# cs301_YourGroupNumber.net
KiCad netlist of a schematic drawn in Altium Designer
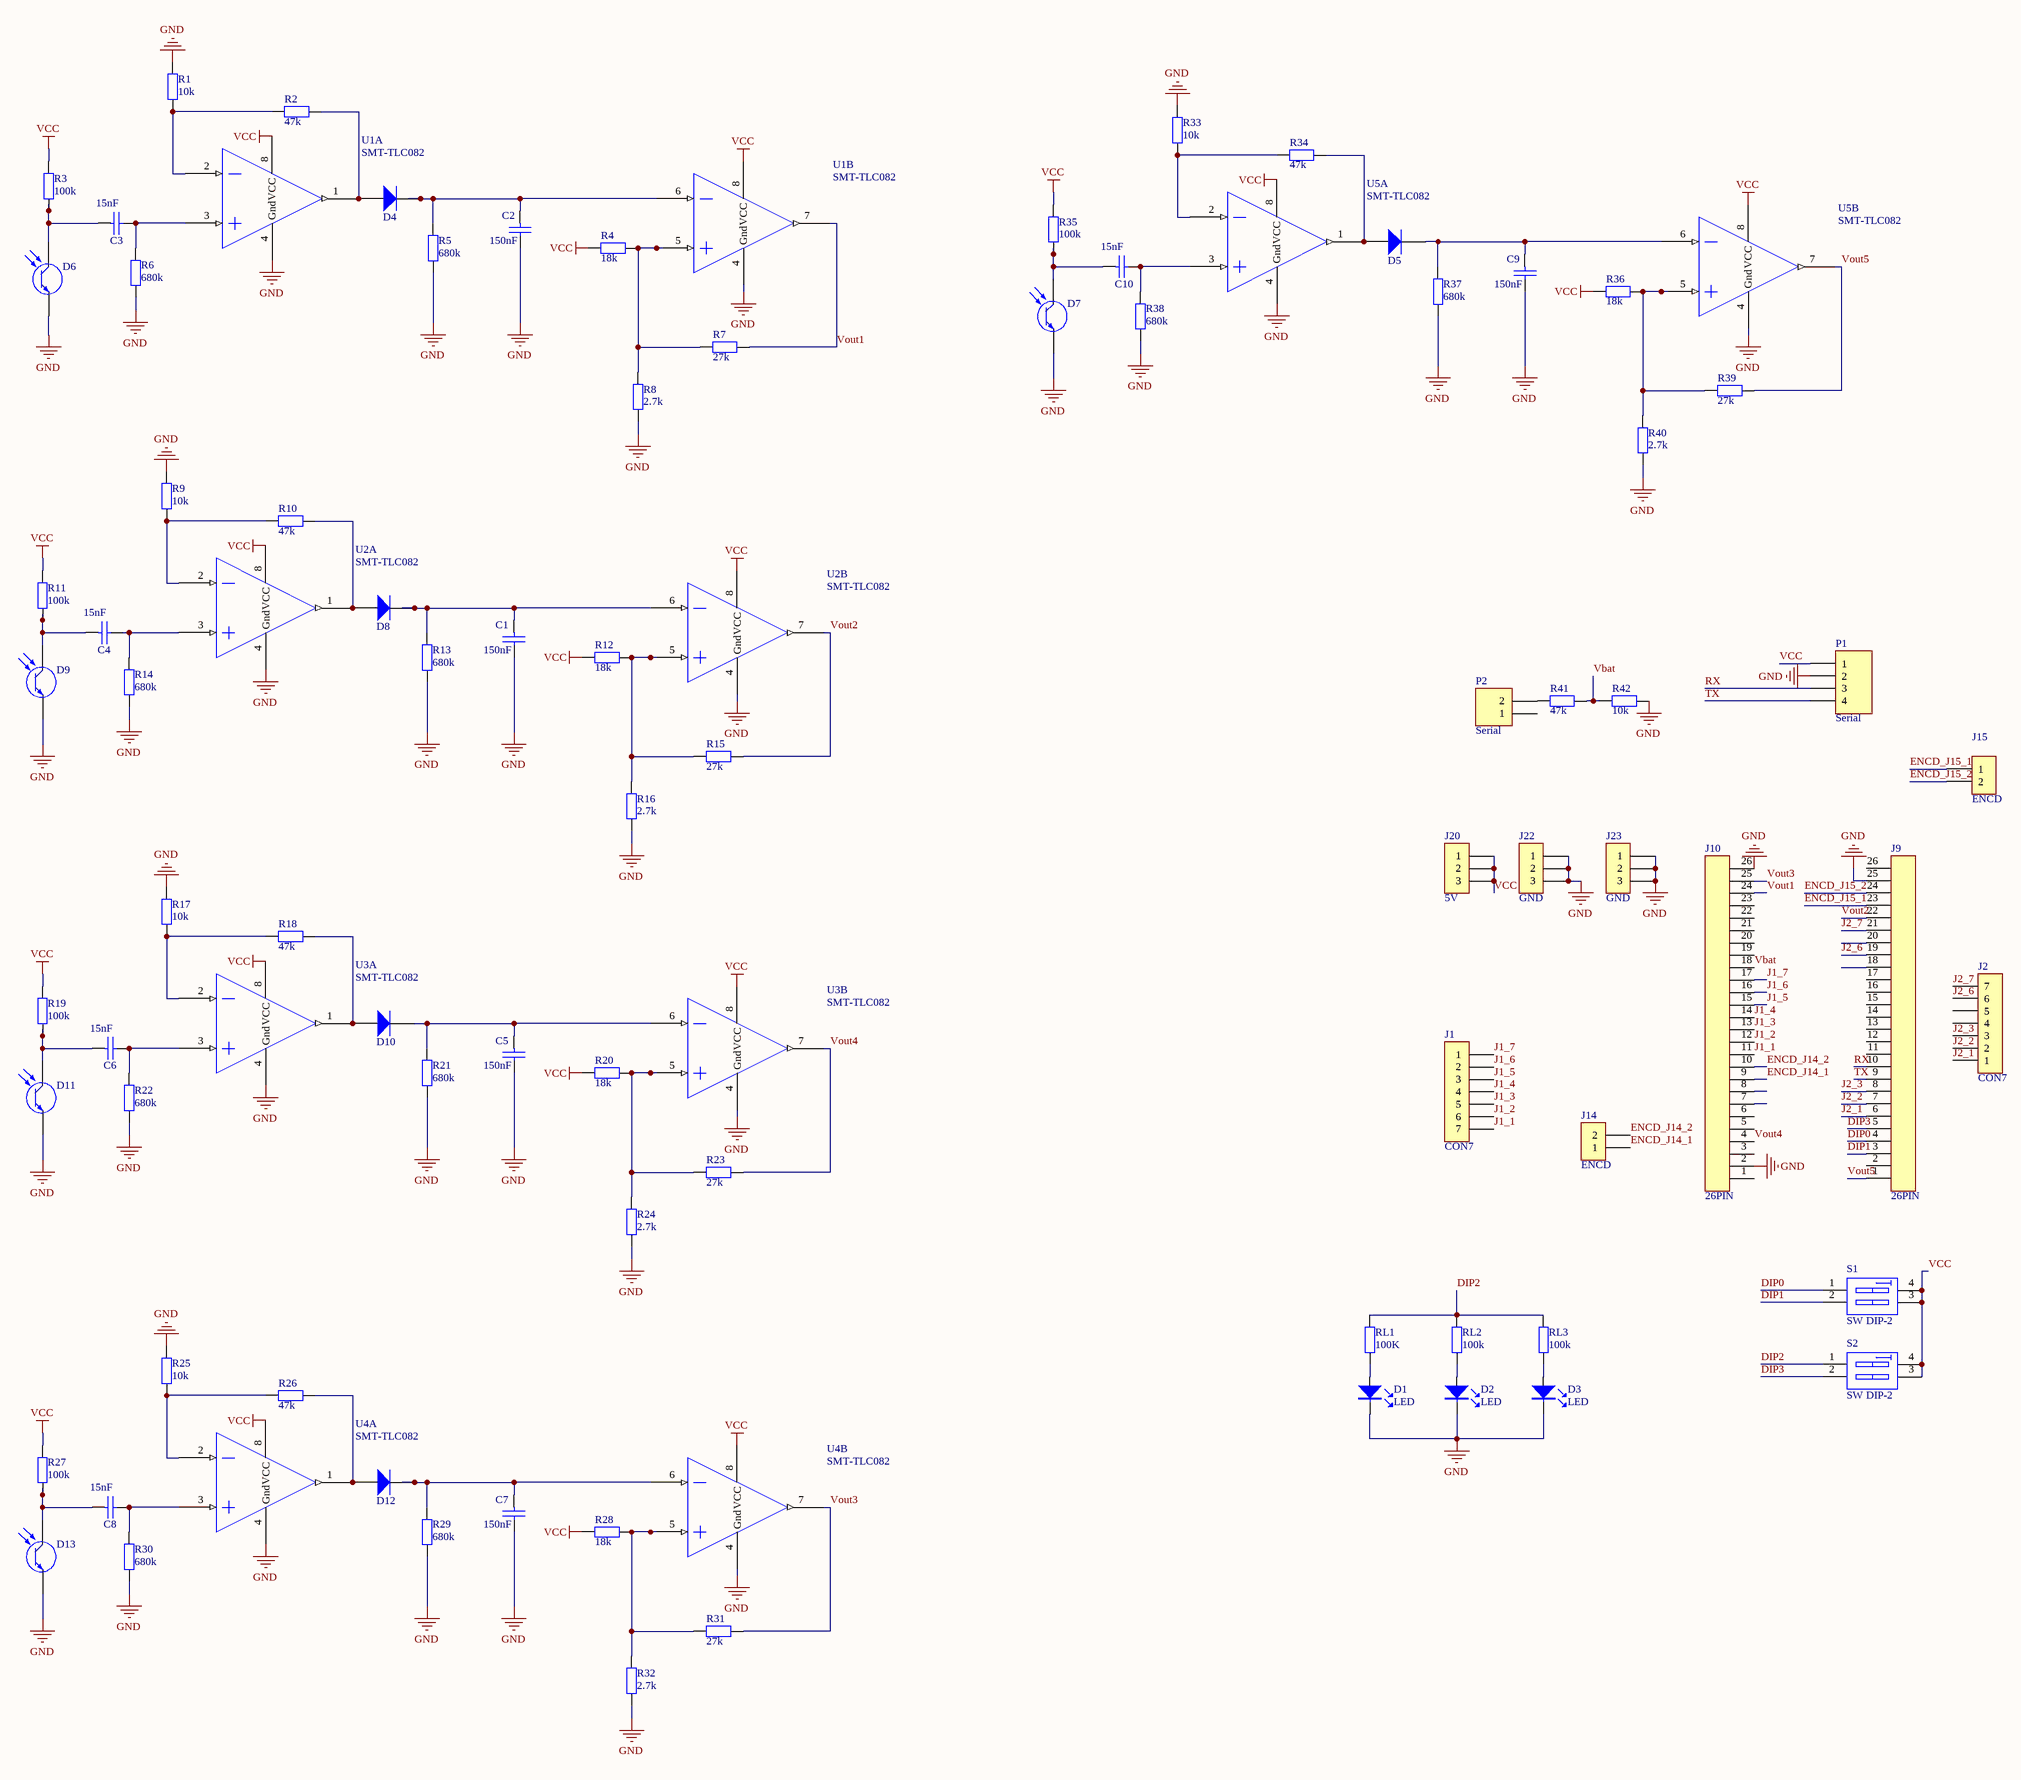
[diagram p0: cs301_YourGroupNumber.SchDoc]

(export (version "E")
  (design (tool "Eeschema 10.0.6"))
  (components
    (comp (ref "C1")
      (value "150nF")
      (footprint "ECE-CAPC1608-0603SM")
      (description "CAP CER 150nF 25V X7R SM0603")
      (libsource (lib "EceParts") (part "Cap"))
    )
    (comp (ref "C2")
      (value "150nF")
      (footprint "ECE-CAPC1608-0603SM")
      (description "CAP CER 150nF 25V X7R SM0603")
      (libsource (lib "EceParts") (part "Cap"))
    )
    (comp (ref "C3")
      (value "15nF")
      (footprint "ECE-CAPC1608-0603SM")
      (description "CAP CER 15nF 50V X7R SM0603")
      (libsource (lib "EceParts") (part "Cap"))
    )
    (comp (ref "C4")
      (value "15nF")
      (footprint "ECE-CAPC1608-0603SM")
      (description "CAP CER 15nF 50V X7R SM0603")
      (libsource (lib "EceParts") (part "Cap"))
    )
    (comp (ref "C5")
      (value "150nF")
      (footprint "ECE-CAPC1608-0603SM")
      (description "CAP CER 150nF 25V X7R SM0603")
      (libsource (lib "EceParts") (part "Cap"))
    )
    (comp (ref "C6")
      (value "15nF")
      (footprint "ECE-CAPC1608-0603SM")
      (description "CAP CER 15nF 50V X7R SM0603")
      (libsource (lib "EceParts") (part "Cap"))
    )
    (comp (ref "C7")
      (value "150nF")
      (footprint "ECE-CAPC1608-0603SM")
      (description "CAP CER 150nF 25V X7R SM0603")
      (libsource (lib "EceParts") (part "Cap"))
    )
    (comp (ref "C8")
      (value "15nF")
      (footprint "ECE-CAPC1608-0603SM")
      (description "CAP CER 15nF 50V X7R SM0603")
      (libsource (lib "EceParts") (part "Cap"))
    )
    (comp (ref "C9")
      (value "150nF")
      (footprint "ECE-CAPC1608-0603SM")
      (description "CAP CER 150nF 25V X7R SM0603")
      (libsource (lib "EceParts") (part "Cap"))
    )
    (comp (ref "C10")
      (value "15nF")
      (footprint "ECE-CAPC1608-0603SM")
      (description "CAP CER 15nF 50V X7R SM0603")
      (libsource (lib "EceParts") (part "Cap"))
    )
    (comp (ref "D1") (value "LED") (footprint "LED0.1/5MM") (libsource (lib "COMSYS301_2013") (part "LED")))
    (comp (ref "D2") (value "LED") (footprint "LED0.1/5MM") (libsource (lib "COMSYS301_2013") (part "LED")))
    (comp (ref "D3") (value "LED") (footprint "LED0.1/5MM") (libsource (lib "COMSYS301_2013") (part "LED")))
    (comp (ref "D4")
      (value "1N4148W-7-F")
      (footprint "ECE-DIO-SOD123SM")
      (description "DIODE GEN PURPOSE 300mA SM")
      (libsource (lib "EceParts") (part "Diode"))
    )
    (comp (ref "D5")
      (value "1N4148W-7-F")
      (footprint "ECE-DIO-SOD123SM")
      (description "DIODE GEN PURPOSE 300mA SM")
      (libsource (lib "EceParts") (part "Diode"))
    )
    (comp (ref "D6")
      (value "TEMT6200")
      (footprint "ECE-SENSOR-0805SM")
      (description "LIGHT SENSOR TEMT6200 SM")
      (libsource (lib "EceParts") (part "TEMT6200"))
    )
    (comp (ref "D7")
      (value "TEMT6200")
      (footprint "ECE-SENSOR-0805SM")
      (description "LIGHT SENSOR TEMT6200 SM")
      (libsource (lib "EceParts") (part "TEMT6200"))
    )
    (comp (ref "D8")
      (value "1N4148W-7-F")
      (footprint "ECE-DIO-SOD123SM")
      (description "DIODE GEN PURPOSE 300mA SM")
      (libsource (lib "EceParts") (part "Diode"))
    )
    (comp (ref "D9")
      (value "TEMT6200")
      (footprint "ECE-SENSOR-0805SM")
      (description "LIGHT SENSOR TEMT6200 SM")
      (libsource (lib "EceParts") (part "TEMT6200"))
    )
    (comp (ref "D10")
      (value "1N4148W-7-F")
      (footprint "ECE-DIO-SOD123SM")
      (description "DIODE GEN PURPOSE 300mA SM")
      (libsource (lib "EceParts") (part "Diode"))
    )
    (comp (ref "D11")
      (value "TEMT6200")
      (footprint "ECE-SENSOR-0805SM")
      (description "LIGHT SENSOR TEMT6200 SM")
      (libsource (lib "EceParts") (part "TEMT6200"))
    )
    (comp (ref "D12")
      (value "1N4148W-7-F")
      (footprint "ECE-DIO-SOD123SM")
      (description "DIODE GEN PURPOSE 300mA SM")
      (libsource (lib "EceParts") (part "Diode"))
    )
    (comp (ref "D13")
      (value "TEMT6200")
      (footprint "ECE-SENSOR-0805SM")
      (description "LIGHT SENSOR TEMT6200 SM")
      (libsource (lib "EceParts") (part "TEMT6200"))
    )
    (comp (ref "J1")
      (value "CON7")
      (footprint "SIP7")
      (description "Connector")
      (libsource (lib "") (part "CON7_1"))
    )
    (comp (ref "J2")
      (value "CON7")
      (footprint "SIP7")
      (description "Connector")
      (libsource (lib "Miscellaneous Devices") (part "CON7"))
    )
    (comp (ref "J9") (value "26PIN") (footprint "SIP26") (libsource (lib "") (part "26PIN_1")))
    (comp (ref "J10")
      (value "26PIN")
      (footprint "SIP26")
      (libsource (lib "Miscellaneous Devices") (part "26PIN"))
    )
    (comp (ref "J14")
      (value "ENCD")
      (footprint "sip2")
      (description "Connector")
      (libsource (lib "Miscellaneous Devices") (part "CON2"))
    )
    (comp (ref "J15")
      (value "ENCD")
      (footprint "sip2")
      (description "Connector")
      (libsource (lib "") (part "CON2_1"))
    )
    (comp (ref "J20")
      (value "5V")
      (footprint "sip3")
      (description "Connector")
      (libsource (lib "Miscellaneous Devices") (part "CON3"))
    )
    (comp (ref "J22")
      (value "GND")
      (footprint "sip3")
      (description "Connector")
      (libsource (lib "Miscellaneous Devices") (part "CON3"))
    )
    (comp (ref "J23")
      (value "GND")
      (footprint "sip3")
      (description "Connector")
      (libsource (lib "Miscellaneous Devices") (part "CON3"))
    )
    (comp (ref "P1")
      (value "Serial")
      (footprint "ece-HDR1X4")
      (description "Header, 4-Pin")
      (fields (field (name "PUBLISHER") "Altium Limited"))
      (libsource (lib "ece components") (part "Header 4"))
    )
    (comp (ref "P2")
      (value "Serial")
      (footprint "HDR1X2")
      (description "Header, 2-Pin")
      (fields (field (name "PUBLISHER") "Altium Limited"))
      (libsource (lib "Miscellaneous Connectors") (part "Header 2"))
    )
    (comp (ref "R1")
      (value "10k")
      (footprint "RESC2012-0805SM")
      (description "SM resistor")
      (libsource (lib "") (part "Res SM 0805_1"))
    )
    (comp (ref "R2")
      (value "47k")
      (footprint "RESC2012-0805SM")
      (description "SM resistor")
      (libsource (lib "ece components") (part "Res SM 0805"))
    )
    (comp (ref "R3")
      (value "100k")
      (footprint "RESC2012-0805SM")
      (description "SM resistor")
      (libsource (lib "") (part "Res SM 0805_1"))
    )
    (comp (ref "R4")
      (value "18k")
      (footprint "RESC2012-0805SM")
      (description "SM resistor")
      (libsource (lib "ece components") (part "Res SM 0805"))
    )
    (comp (ref "R5")
      (value "680k")
      (footprint "RESC2012-0805SM")
      (description "SM resistor")
      (libsource (lib "") (part "Res SM 0805_1"))
    )
    (comp (ref "R6")
      (value "680k")
      (footprint "RESC2012-0805SM")
      (description "SM resistor")
      (libsource (lib "") (part "Res SM 0805_1"))
    )
    (comp (ref "R7")
      (value "27k")
      (footprint "RESC2012-0805SM")
      (description "SM resistor")
      (libsource (lib "ece components") (part "Res SM 0805"))
    )
    (comp (ref "R8")
      (value "2.7k")
      (footprint "RESC2012-0805SM")
      (description "SM resistor")
      (libsource (lib "") (part "Res SM 0805_1"))
    )
    (comp (ref "R9")
      (value "10k")
      (footprint "RESC2012-0805SM")
      (description "SM resistor")
      (libsource (lib "") (part "Res SM 0805_1"))
    )
    (comp (ref "R10")
      (value "47k")
      (footprint "RESC2012-0805SM")
      (description "SM resistor")
      (libsource (lib "ece components") (part "Res SM 0805"))
    )
    (comp (ref "R11")
      (value "100k")
      (footprint "RESC2012-0805SM")
      (description "SM resistor")
      (libsource (lib "") (part "Res SM 0805_1"))
    )
    (comp (ref "R12")
      (value "18k")
      (footprint "RESC2012-0805SM")
      (description "SM resistor")
      (libsource (lib "ece components") (part "Res SM 0805"))
    )
    (comp (ref "R13")
      (value "680k")
      (footprint "RESC2012-0805SM")
      (description "SM resistor")
      (libsource (lib "") (part "Res SM 0805_1"))
    )
    (comp (ref "R14")
      (value "680k")
      (footprint "RESC2012-0805SM")
      (description "SM resistor")
      (libsource (lib "") (part "Res SM 0805_1"))
    )
    (comp (ref "R15")
      (value "27k")
      (footprint "RESC2012-0805SM")
      (description "SM resistor")
      (libsource (lib "ece components") (part "Res SM 0805"))
    )
    (comp (ref "R16")
      (value "2.7k")
      (footprint "RESC2012-0805SM")
      (description "SM resistor")
      (libsource (lib "") (part "Res SM 0805_1"))
    )
    (comp (ref "R17")
      (value "10k")
      (footprint "RESC2012-0805SM")
      (description "SM resistor")
      (libsource (lib "") (part "Res SM 0805_1"))
    )
    (comp (ref "R18")
      (value "47k")
      (footprint "RESC2012-0805SM")
      (description "SM resistor")
      (libsource (lib "ece components") (part "Res SM 0805"))
    )
    (comp (ref "R19")
      (value "100k")
      (footprint "RESC2012-0805SM")
      (description "SM resistor")
      (libsource (lib "") (part "Res SM 0805_1"))
    )
    (comp (ref "R20")
      (value "18k")
      (footprint "RESC2012-0805SM")
      (description "SM resistor")
      (libsource (lib "ece components") (part "Res SM 0805"))
    )
    (comp (ref "R21")
      (value "680k")
      (footprint "RESC2012-0805SM")
      (description "SM resistor")
      (libsource (lib "") (part "Res SM 0805_1"))
    )
    (comp (ref "R22")
      (value "680k")
      (footprint "RESC2012-0805SM")
      (description "SM resistor")
      (libsource (lib "") (part "Res SM 0805_1"))
    )
    (comp (ref "R23")
      (value "27k")
      (footprint "RESC2012-0805SM")
      (description "SM resistor")
      (libsource (lib "ece components") (part "Res SM 0805"))
    )
    (comp (ref "R24")
      (value "2.7k")
      (footprint "RESC2012-0805SM")
      (description "SM resistor")
      (libsource (lib "") (part "Res SM 0805_1"))
    )
    (comp (ref "R25")
      (value "10k")
      (footprint "RESC2012-0805SM")
      (description "SM resistor")
      (libsource (lib "") (part "Res SM 0805_1"))
    )
    (comp (ref "R26")
      (value "47k")
      (footprint "RESC2012-0805SM")
      (description "SM resistor")
      (libsource (lib "ece components") (part "Res SM 0805"))
    )
    (comp (ref "R27")
      (value "100k")
      (footprint "RESC2012-0805SM")
      (description "SM resistor")
      (libsource (lib "") (part "Res SM 0805_1"))
    )
    (comp (ref "R28")
      (value "18k")
      (footprint "RESC2012-0805SM")
      (description "SM resistor")
      (libsource (lib "ece components") (part "Res SM 0805"))
    )
    (comp (ref "R29")
      (value "680k")
      (footprint "RESC2012-0805SM")
      (description "SM resistor")
      (libsource (lib "") (part "Res SM 0805_1"))
    )
    (comp (ref "R30")
      (value "680k")
      (footprint "RESC2012-0805SM")
      (description "SM resistor")
      (libsource (lib "") (part "Res SM 0805_1"))
    )
    (comp (ref "R31")
      (value "27k")
      (footprint "RESC2012-0805SM")
      (description "SM resistor")
      (libsource (lib "ece components") (part "Res SM 0805"))
    )
    (comp (ref "R32")
      (value "2.7k")
      (footprint "RESC2012-0805SM")
      (description "SM resistor")
      (libsource (lib "") (part "Res SM 0805_1"))
    )
    (comp (ref "R33")
      (value "10k")
      (footprint "RESC2012-0805SM")
      (description "SM resistor")
      (libsource (lib "") (part "Res SM 0805_1"))
    )
    (comp (ref "R34")
      (value "47k")
      (footprint "RESC2012-0805SM")
      (description "SM resistor")
      (libsource (lib "ece components") (part "Res SM 0805"))
    )
    (comp (ref "R35")
      (value "100k")
      (footprint "RESC2012-0805SM")
      (description "SM resistor")
      (libsource (lib "") (part "Res SM 0805_1"))
    )
    (comp (ref "R36")
      (value "18k")
      (footprint "RESC2012-0805SM")
      (description "SM resistor")
      (libsource (lib "ece components") (part "Res SM 0805"))
    )
    (comp (ref "R37")
      (value "680k")
      (footprint "RESC2012-0805SM")
      (description "SM resistor")
      (libsource (lib "") (part "Res SM 0805_1"))
    )
    (comp (ref "R38")
      (value "680k")
      (footprint "RESC2012-0805SM")
      (description "SM resistor")
      (libsource (lib "") (part "Res SM 0805_1"))
    )
    (comp (ref "R39")
      (value "27k")
      (footprint "RESC2012-0805SM")
      (description "SM resistor")
      (libsource (lib "ece components") (part "Res SM 0805"))
    )
    (comp (ref "R40")
      (value "2.7k")
      (footprint "RESC2012-0805SM")
      (description "SM resistor")
      (libsource (lib "") (part "Res SM 0805_1"))
    )
    (comp (ref "R41")
      (value "47k")
      (footprint "RESC2012-0805SM")
      (description "SM resistor")
      (libsource (lib "ece components") (part "Res SM 0805"))
    )
    (comp (ref "R42")
      (value "10k")
      (footprint "RESC2012-0805SM")
      (description "SM resistor")
      (libsource (lib "ece components") (part "Res SM 0805"))
    )
    (comp (ref "RL1")
      (value "100K")
      (footprint "RESC2012-0805SM")
      (description "SM resistor")
      (libsource (lib "") (part "Res SM 0805_1"))
    )
    (comp (ref "RL2")
      (value "100k")
      (footprint "RESC2012-0805SM")
      (description "SM resistor")
      (libsource (lib "") (part "Res SM 0805_1"))
    )
    (comp (ref "RL3")
      (value "100k")
      (footprint "RESC2012-0805SM")
      (description "SM resistor")
      (libsource (lib "") (part "Res SM 0805_1"))
    )
    (comp (ref "S1")
      (value "SW DIP-2")
      (footprint "DIP-4")
      (description "DIP Switch, 2 Position, SPST")
      (fields (field (name "PUBLISHER") "Altium Limited"))
      (libsource (lib "Miscellaneous Devices") (part "SW DIP-2"))
    )
    (comp (ref "S2")
      (value "SW DIP-2")
      (footprint "DIP-4")
      (description "DIP Switch, 2 Position, SPST")
      (fields (field (name "PUBLISHER") "Altium Limited"))
      (libsource (lib "Miscellaneous Devices") (part "SW DIP-2"))
    )
    (comp (ref "U1") (value "SMT-TLC082") (footprint "SO-8") (libsource (lib "EE209") (part "SMT-TLC082")))
    (comp (ref "U2") (value "SMT-TLC082") (footprint "SO-8") (libsource (lib "EE209") (part "SMT-TLC082")))
    (comp (ref "U3") (value "SMT-TLC082") (footprint "SO-8") (libsource (lib "EE209") (part "SMT-TLC082")))
    (comp (ref "U4") (value "SMT-TLC082") (footprint "SO-8") (libsource (lib "EE209") (part "SMT-TLC082")))
    (comp (ref "U5") (value "SMT-TLC082") (footprint "SO-8") (libsource (lib "EE209") (part "SMT-TLC082")))
  )
  (nets
    (net (code "1") (name "/DIP0") (class "Default")
      (node (ref "J9") (pin "4") (pinfunction "4_4") (pintype "passive"))
      (node (ref "S1") (pin "1") (pinfunction "A1_1") (pintype "passive"))
    )
    (net (code "2") (name "/DIP1") (class "Default")
      (node (ref "J9") (pin "3") (pinfunction "3_3") (pintype "passive"))
      (node (ref "S1") (pin "2") (pinfunction "A2_2") (pintype "passive"))
    )
    (net (code "3") (name "/DIP2") (class "Default")
      (node (ref "RL1") (pin "2") (pinfunction "2_2") (pintype "passive"))
      (node (ref "RL2") (pin "2") (pinfunction "2_2") (pintype "passive"))
      (node (ref "RL3") (pin "2") (pinfunction "2_2") (pintype "passive"))
      (node (ref "S2") (pin "1") (pinfunction "A1_1") (pintype "passive"))
    )
    (net (code "4") (name "/DIP3") (class "Default")
      (node (ref "J9") (pin "5") (pinfunction "5_5") (pintype "passive"))
      (node (ref "S2") (pin "2") (pinfunction "A2_2") (pintype "passive"))
    )
    (net (code "5") (name "/ENCD_J14_1") (class "Default")
      (node (ref "J10") (pin "9") (pinfunction "9_9") (pintype "passive"))
      (node (ref "J14") (pin "1") (pinfunction "1_1") (pintype "passive"))
    )
    (net (code "6") (name "/ENCD_J14_2") (class "Default")
      (node (ref "J10") (pin "10") (pinfunction "10_10") (pintype "passive"))
      (node (ref "J14") (pin "2") (pinfunction "2_2") (pintype "passive"))
    )
    (net (code "7") (name "/ENCD_J15_1") (class "Default")
      (node (ref "J15") (pin "1") (pinfunction "1_1") (pintype "passive"))
      (node (ref "J9") (pin "23") (pinfunction "23_23") (pintype "passive"))
    )
    (net (code "8") (name "/ENCD_J15_2") (class "Default")
      (node (ref "J15") (pin "2") (pinfunction "2_2") (pintype "passive"))
      (node (ref "J9") (pin "24") (pinfunction "24_24") (pintype "passive"))
    )
    (net (code "9") (name "/J1_1") (class "Default")
      (node (ref "J1") (pin "7") (pinfunction "7_7") (pintype "passive"))
      (node (ref "J10") (pin "11") (pinfunction "11_11") (pintype "passive"))
    )
    (net (code "10") (name "/J1_2") (class "Default")
      (node (ref "J1") (pin "6") (pinfunction "6_6") (pintype "passive"))
      (node (ref "J10") (pin "12") (pinfunction "12_12") (pintype "passive"))
    )
    (net (code "11") (name "/J1_3") (class "Default")
      (node (ref "J1") (pin "5") (pinfunction "5_5") (pintype "passive"))
      (node (ref "J10") (pin "13") (pinfunction "13_13") (pintype "passive"))
    )
    (net (code "12") (name "/J1_4") (class "Default")
      (node (ref "J1") (pin "4") (pinfunction "4_4") (pintype "passive"))
      (node (ref "J10") (pin "14") (pinfunction "14_14") (pintype "passive"))
    )
    (net (code "13") (name "/J1_5") (class "Default")
      (node (ref "J1") (pin "3") (pinfunction "3_3") (pintype "passive"))
      (node (ref "J10") (pin "15") (pinfunction "15_15") (pintype "passive"))
    )
    (net (code "14") (name "/J1_6") (class "Default")
      (node (ref "J1") (pin "2") (pinfunction "2_2") (pintype "passive"))
      (node (ref "J10") (pin "16") (pinfunction "16_16") (pintype "passive"))
    )
    (net (code "15") (name "/J1_7") (class "Default")
      (node (ref "J1") (pin "1") (pinfunction "1_1") (pintype "passive"))
      (node (ref "J10") (pin "17") (pinfunction "17_17") (pintype "passive"))
    )
    (net (code "16") (name "/J2_1") (class "Default")
      (node (ref "J2") (pin "1") (pinfunction "1_1") (pintype "passive"))
      (node (ref "J9") (pin "6") (pinfunction "6_6") (pintype "passive"))
    )
    (net (code "17") (name "/J2_2") (class "Default")
      (node (ref "J2") (pin "2") (pinfunction "2_2") (pintype "passive"))
      (node (ref "J9") (pin "7") (pinfunction "7_7") (pintype "passive"))
    )
    (net (code "18") (name "/J2_3") (class "Default")
      (node (ref "J2") (pin "3") (pinfunction "3_3") (pintype "passive"))
      (node (ref "J9") (pin "8") (pinfunction "8_8") (pintype "passive"))
    )
    (net (code "19") (name "/J2_6") (class "Default")
      (node (ref "J2") (pin "6") (pinfunction "6_6") (pintype "passive"))
      (node (ref "J9") (pin "19") (pinfunction "19_19") (pintype "passive"))
    )
    (net (code "20") (name "/J2_7") (class "Default")
      (node (ref "J2") (pin "7") (pinfunction "7_7") (pintype "passive"))
      (node (ref "J9") (pin "21") (pinfunction "21_21") (pintype "passive"))
    )
    (net (code "21") (name "/RX") (class "Default")
      (node (ref "J9") (pin "10") (pinfunction "10_10") (pintype "passive"))
      (node (ref "P1") (pin "3") (pinfunction "3_3") (pintype "passive"))
    )
    (net (code "22") (name "/TX") (class "Default")
      (node (ref "J9") (pin "9") (pinfunction "9_9") (pintype "passive"))
      (node (ref "P1") (pin "4") (pinfunction "4_4") (pintype "passive"))
    )
    (net (code "23") (name "/Vbat") (class "Default")
      (node (ref "J10") (pin "18") (pinfunction "18_18") (pintype "passive"))
      (node (ref "R41") (pin "1") (pinfunction "1_1") (pintype "passive"))
      (node (ref "R42") (pin "2") (pinfunction "2_2") (pintype "passive"))
    )
    (net (code "24") (name "/Vout1") (class "Default")
      (node (ref "J10") (pin "24") (pinfunction "24_24") (pintype "passive"))
      (node (ref "R7") (pin "1") (pinfunction "1_1") (pintype "passive"))
      (node (ref "U1") (pin "7") (pinfunction "OUT2_7") (pintype "output"))
    )
    (net (code "25") (name "/Vout2") (class "Default")
      (node (ref "J9") (pin "22") (pinfunction "22_22") (pintype "passive"))
      (node (ref "R15") (pin "1") (pinfunction "1_1") (pintype "passive"))
      (node (ref "U2") (pin "7") (pinfunction "OUT2_7") (pintype "output"))
    )
    (net (code "26") (name "/Vout3") (class "Default")
      (node (ref "J10") (pin "25") (pinfunction "25_25") (pintype "passive"))
      (node (ref "R31") (pin "1") (pinfunction "1_1") (pintype "passive"))
      (node (ref "U4") (pin "7") (pinfunction "OUT2_7") (pintype "output"))
    )
    (net (code "27") (name "/Vout4") (class "Default")
      (node (ref "J10") (pin "4") (pinfunction "4_4") (pintype "passive"))
      (node (ref "R23") (pin "1") (pinfunction "1_1") (pintype "passive"))
      (node (ref "U3") (pin "7") (pinfunction "OUT2_7") (pintype "output"))
    )
    (net (code "28") (name "/Vout5") (class "Default")
      (node (ref "J9") (pin "1") (pinfunction "1_1") (pintype "passive"))
      (node (ref "R39") (pin "1") (pinfunction "1_1") (pintype "passive"))
      (node (ref "U5") (pin "7") (pinfunction "OUT2_7") (pintype "output"))
    )
    (net (code "29") (name "GND") (class "Default")
      (node (ref "C1") (pin "2") (pinfunction "2_2") (pintype "passive"))
      (node (ref "C2") (pin "2") (pinfunction "2_2") (pintype "passive"))
      (node (ref "C5") (pin "2") (pinfunction "2_2") (pintype "passive"))
      (node (ref "C7") (pin "2") (pinfunction "2_2") (pintype "passive"))
      (node (ref "C9") (pin "2") (pinfunction "2_2") (pintype "passive"))
      (node (ref "D1") (pin "K") (pinfunction "2_K") (pintype "passive"))
      (node (ref "D11") (pin "1") (pinfunction "E_1") (pintype "passive"))
      (node (ref "D13") (pin "1") (pinfunction "E_1") (pintype "passive"))
      (node (ref "D2") (pin "K") (pinfunction "2_K") (pintype "passive"))
      (node (ref "D3") (pin "K") (pinfunction "2_K") (pintype "passive"))
      (node (ref "D6") (pin "1") (pinfunction "E_1") (pintype "passive"))
      (node (ref "D7") (pin "1") (pinfunction "E_1") (pintype "passive"))
      (node (ref "D9") (pin "1") (pinfunction "E_1") (pintype "passive"))
      (node (ref "J10") (pin "2") (pinfunction "2_2") (pintype "passive"))
      (node (ref "J10") (pin "26") (pinfunction "26_26") (pintype "passive"))
      (node (ref "J22") (pin "1") (pinfunction "1_1") (pintype "passive"))
      (node (ref "J22") (pin "2") (pinfunction "2_2") (pintype "passive"))
      (node (ref "J22") (pin "3") (pinfunction "3_3") (pintype "passive"))
      (node (ref "J23") (pin "1") (pinfunction "1_1") (pintype "passive"))
      (node (ref "J23") (pin "2") (pinfunction "2_2") (pintype "passive"))
      (node (ref "J23") (pin "3") (pinfunction "3_3") (pintype "passive"))
      (node (ref "J9") (pin "25") (pinfunction "25_25") (pintype "passive"))
      (node (ref "P1") (pin "2") (pinfunction "2_2") (pintype "passive"))
      (node (ref "R1") (pin "2") (pinfunction "2_2") (pintype "passive"))
      (node (ref "R13") (pin "1") (pinfunction "1_1") (pintype "passive"))
      (node (ref "R14") (pin "1") (pinfunction "1_1") (pintype "passive"))
      (node (ref "R16") (pin "1") (pinfunction "1_1") (pintype "passive"))
      (node (ref "R17") (pin "2") (pinfunction "2_2") (pintype "passive"))
      (node (ref "R21") (pin "1") (pinfunction "1_1") (pintype "passive"))
      (node (ref "R22") (pin "1") (pinfunction "1_1") (pintype "passive"))
      (node (ref "R24") (pin "1") (pinfunction "1_1") (pintype "passive"))
      (node (ref "R25") (pin "2") (pinfunction "2_2") (pintype "passive"))
      (node (ref "R29") (pin "1") (pinfunction "1_1") (pintype "passive"))
      (node (ref "R30") (pin "1") (pinfunction "1_1") (pintype "passive"))
      (node (ref "R32") (pin "1") (pinfunction "1_1") (pintype "passive"))
      (node (ref "R33") (pin "2") (pinfunction "2_2") (pintype "passive"))
      (node (ref "R37") (pin "1") (pinfunction "1_1") (pintype "passive"))
      (node (ref "R38") (pin "1") (pinfunction "1_1") (pintype "passive"))
      (node (ref "R40") (pin "1") (pinfunction "1_1") (pintype "passive"))
      (node (ref "R42") (pin "1") (pinfunction "1_1") (pintype "passive"))
      (node (ref "R5") (pin "1") (pinfunction "1_1") (pintype "passive"))
      (node (ref "R6") (pin "1") (pinfunction "1_1") (pintype "passive"))
      (node (ref "R8") (pin "1") (pinfunction "1_1") (pintype "passive"))
      (node (ref "R9") (pin "2") (pinfunction "2_2") (pintype "passive"))
      (node (ref "U1") (pin "4") (pinfunction "Gnd_4") (pintype "power_in"))
      (node (ref "U2") (pin "4") (pinfunction "Gnd_4") (pintype "power_in"))
      (node (ref "U3") (pin "4") (pinfunction "Gnd_4") (pintype "power_in"))
      (node (ref "U4") (pin "4") (pinfunction "Gnd_4") (pintype "power_in"))
      (node (ref "U5") (pin "4") (pinfunction "Gnd_4") (pintype "power_in"))
    )
    (net (code "30") (name "Net-(D1-1)") (class "Default")
      (node (ref "D1") (pin "A") (pinfunction "1_A") (pintype "passive"))
      (node (ref "RL1") (pin "1") (pinfunction "1_1") (pintype "passive"))
    )
    (net (code "31") (name "Net-(D2-1)") (class "Default")
      (node (ref "D2") (pin "A") (pinfunction "1_A") (pintype "passive"))
      (node (ref "RL2") (pin "1") (pinfunction "1_1") (pintype "passive"))
    )
    (net (code "32") (name "Net-(D3-1)") (class "Default")
      (node (ref "D3") (pin "A") (pinfunction "1_A") (pintype "passive"))
      (node (ref "RL3") (pin "1") (pinfunction "1_1") (pintype "passive"))
    )
    (net (code "33") (name "Net-(D4-A)") (class "Default")
      (node (ref "D4") (pin "1") (pinfunction "A_1") (pintype "passive"))
      (node (ref "R2") (pin "1") (pinfunction "1_1") (pintype "passive"))
      (node (ref "U1") (pin "1") (pinfunction "OUT1_1") (pintype "output"))
    )
    (net (code "34") (name "Net-(D4-K)") (class "Default")
      (node (ref "C2") (pin "1") (pinfunction "1_1") (pintype "passive"))
      (node (ref "D4") (pin "2") (pinfunction "K_2") (pintype "passive"))
      (node (ref "R5") (pin "2") (pinfunction "2_2") (pintype "passive"))
      (node (ref "U1") (pin "6") (pinfunction "IN2(-)_6") (pintype "input"))
    )
    (net (code "35") (name "Net-(D5-A)") (class "Default")
      (node (ref "D5") (pin "1") (pinfunction "A_1") (pintype "passive"))
      (node (ref "R34") (pin "1") (pinfunction "1_1") (pintype "passive"))
      (node (ref "U5") (pin "1") (pinfunction "OUT1_1") (pintype "output"))
    )
    (net (code "36") (name "Net-(D5-K)") (class "Default")
      (node (ref "C9") (pin "1") (pinfunction "1_1") (pintype "passive"))
      (node (ref "D5") (pin "2") (pinfunction "K_2") (pintype "passive"))
      (node (ref "R37") (pin "2") (pinfunction "2_2") (pintype "passive"))
      (node (ref "U5") (pin "6") (pinfunction "IN2(-)_6") (pintype "input"))
    )
    (net (code "37") (name "Net-(D6-C)") (class "Default")
      (node (ref "C3") (pin "1") (pinfunction "1_1") (pintype "passive"))
      (node (ref "D6") (pin "2") (pinfunction "C_2") (pintype "passive"))
      (node (ref "R3") (pin "1") (pinfunction "1_1") (pintype "passive"))
    )
    (net (code "38") (name "Net-(D7-C)") (class "Default")
      (node (ref "C10") (pin "1") (pinfunction "1_1") (pintype "passive"))
      (node (ref "D7") (pin "2") (pinfunction "C_2") (pintype "passive"))
      (node (ref "R35") (pin "1") (pinfunction "1_1") (pintype "passive"))
    )
    (net (code "39") (name "Net-(D8-A)") (class "Default")
      (node (ref "D8") (pin "1") (pinfunction "A_1") (pintype "passive"))
      (node (ref "R10") (pin "1") (pinfunction "1_1") (pintype "passive"))
      (node (ref "U2") (pin "1") (pinfunction "OUT1_1") (pintype "output"))
    )
    (net (code "40") (name "Net-(D8-K)") (class "Default")
      (node (ref "C1") (pin "1") (pinfunction "1_1") (pintype "passive"))
      (node (ref "D8") (pin "2") (pinfunction "K_2") (pintype "passive"))
      (node (ref "R13") (pin "2") (pinfunction "2_2") (pintype "passive"))
      (node (ref "U2") (pin "6") (pinfunction "IN2(-)_6") (pintype "input"))
    )
    (net (code "41") (name "Net-(D9-C)") (class "Default")
      (node (ref "C4") (pin "1") (pinfunction "1_1") (pintype "passive"))
      (node (ref "D9") (pin "2") (pinfunction "C_2") (pintype "passive"))
      (node (ref "R11") (pin "1") (pinfunction "1_1") (pintype "passive"))
    )
    (net (code "42") (name "Net-(D10-A)") (class "Default")
      (node (ref "D10") (pin "1") (pinfunction "A_1") (pintype "passive"))
      (node (ref "R18") (pin "1") (pinfunction "1_1") (pintype "passive"))
      (node (ref "U3") (pin "1") (pinfunction "OUT1_1") (pintype "output"))
    )
    (net (code "43") (name "Net-(D10-K)") (class "Default")
      (node (ref "C5") (pin "1") (pinfunction "1_1") (pintype "passive"))
      (node (ref "D10") (pin "2") (pinfunction "K_2") (pintype "passive"))
      (node (ref "R21") (pin "2") (pinfunction "2_2") (pintype "passive"))
      (node (ref "U3") (pin "6") (pinfunction "IN2(-)_6") (pintype "input"))
    )
    (net (code "44") (name "Net-(D11-C)") (class "Default")
      (node (ref "C6") (pin "1") (pinfunction "1_1") (pintype "passive"))
      (node (ref "D11") (pin "2") (pinfunction "C_2") (pintype "passive"))
      (node (ref "R19") (pin "1") (pinfunction "1_1") (pintype "passive"))
    )
    (net (code "45") (name "Net-(D12-A)") (class "Default")
      (node (ref "D12") (pin "1") (pinfunction "A_1") (pintype "passive"))
      (node (ref "R26") (pin "1") (pinfunction "1_1") (pintype "passive"))
      (node (ref "U4") (pin "1") (pinfunction "OUT1_1") (pintype "output"))
    )
    (net (code "46") (name "Net-(D12-K)") (class "Default")
      (node (ref "C7") (pin "1") (pinfunction "1_1") (pintype "passive"))
      (node (ref "D12") (pin "2") (pinfunction "K_2") (pintype "passive"))
      (node (ref "R29") (pin "2") (pinfunction "2_2") (pintype "passive"))
      (node (ref "U4") (pin "6") (pinfunction "IN2(-)_6") (pintype "input"))
    )
    (net (code "47") (name "Net-(D13-C)") (class "Default")
      (node (ref "C8") (pin "1") (pinfunction "1_1") (pintype "passive"))
      (node (ref "D13") (pin "2") (pinfunction "C_2") (pintype "passive"))
      (node (ref "R27") (pin "1") (pinfunction "1_1") (pintype "passive"))
    )
    (net (code "48") (name "Net-(P2-Pad2)") (class "Default")
      (node (ref "P2") (pin "2") (pinfunction "2_2") (pintype "passive"))
      (node (ref "R41") (pin "2") (pinfunction "2_2") (pintype "passive"))
    )
    (net (code "49") (name "Net-(U1A-IN1(+))") (class "Default")
      (node (ref "C3") (pin "2") (pinfunction "2_2") (pintype "passive"))
      (node (ref "R6") (pin "2") (pinfunction "2_2") (pintype "passive"))
      (node (ref "U1") (pin "3") (pinfunction "IN1(+)_3") (pintype "input"))
    )
    (net (code "50") (name "Net-(U1A-IN1(-))") (class "Default")
      (node (ref "R1") (pin "1") (pinfunction "1_1") (pintype "passive"))
      (node (ref "R2") (pin "2") (pinfunction "2_2") (pintype "passive"))
      (node (ref "U1") (pin "2") (pinfunction "IN1(-)_2") (pintype "input"))
    )
    (net (code "51") (name "Net-(U1B-IN2(+))") (class "Default")
      (node (ref "R4") (pin "1") (pinfunction "1_1") (pintype "passive"))
      (node (ref "R7") (pin "2") (pinfunction "2_2") (pintype "passive"))
      (node (ref "R8") (pin "2") (pinfunction "2_2") (pintype "passive"))
      (node (ref "U1") (pin "5") (pinfunction "IN2(+)_5") (pintype "input"))
    )
    (net (code "52") (name "Net-(U2A-IN1(+))") (class "Default")
      (node (ref "C4") (pin "2") (pinfunction "2_2") (pintype "passive"))
      (node (ref "R14") (pin "2") (pinfunction "2_2") (pintype "passive"))
      (node (ref "U2") (pin "3") (pinfunction "IN1(+)_3") (pintype "input"))
    )
    (net (code "53") (name "Net-(U2A-IN1(-))") (class "Default")
      (node (ref "R10") (pin "2") (pinfunction "2_2") (pintype "passive"))
      (node (ref "R9") (pin "1") (pinfunction "1_1") (pintype "passive"))
      (node (ref "U2") (pin "2") (pinfunction "IN1(-)_2") (pintype "input"))
    )
    (net (code "54") (name "Net-(U2B-IN2(+))") (class "Default")
      (node (ref "R12") (pin "1") (pinfunction "1_1") (pintype "passive"))
      (node (ref "R15") (pin "2") (pinfunction "2_2") (pintype "passive"))
      (node (ref "R16") (pin "2") (pinfunction "2_2") (pintype "passive"))
      (node (ref "U2") (pin "5") (pinfunction "IN2(+)_5") (pintype "input"))
    )
    (net (code "55") (name "Net-(U3A-IN1(+))") (class "Default")
      (node (ref "C6") (pin "2") (pinfunction "2_2") (pintype "passive"))
      (node (ref "R22") (pin "2") (pinfunction "2_2") (pintype "passive"))
      (node (ref "U3") (pin "3") (pinfunction "IN1(+)_3") (pintype "input"))
    )
    (net (code "56") (name "Net-(U3A-IN1(-))") (class "Default")
      (node (ref "R17") (pin "1") (pinfunction "1_1") (pintype "passive"))
      (node (ref "R18") (pin "2") (pinfunction "2_2") (pintype "passive"))
      (node (ref "U3") (pin "2") (pinfunction "IN1(-)_2") (pintype "input"))
    )
    (net (code "57") (name "Net-(U3B-IN2(+))") (class "Default")
      (node (ref "R20") (pin "1") (pinfunction "1_1") (pintype "passive"))
      (node (ref "R23") (pin "2") (pinfunction "2_2") (pintype "passive"))
      (node (ref "R24") (pin "2") (pinfunction "2_2") (pintype "passive"))
      (node (ref "U3") (pin "5") (pinfunction "IN2(+)_5") (pintype "input"))
    )
    (net (code "58") (name "Net-(U4A-IN1(+))") (class "Default")
      (node (ref "C8") (pin "2") (pinfunction "2_2") (pintype "passive"))
      (node (ref "R30") (pin "2") (pinfunction "2_2") (pintype "passive"))
      (node (ref "U4") (pin "3") (pinfunction "IN1(+)_3") (pintype "input"))
    )
    (net (code "59") (name "Net-(U4A-IN1(-))") (class "Default")
      (node (ref "R25") (pin "1") (pinfunction "1_1") (pintype "passive"))
      (node (ref "R26") (pin "2") (pinfunction "2_2") (pintype "passive"))
      (node (ref "U4") (pin "2") (pinfunction "IN1(-)_2") (pintype "input"))
    )
    (net (code "60") (name "Net-(U4B-IN2(+))") (class "Default")
      (node (ref "R28") (pin "1") (pinfunction "1_1") (pintype "passive"))
      (node (ref "R31") (pin "2") (pinfunction "2_2") (pintype "passive"))
      (node (ref "R32") (pin "2") (pinfunction "2_2") (pintype "passive"))
      (node (ref "U4") (pin "5") (pinfunction "IN2(+)_5") (pintype "input"))
    )
    (net (code "61") (name "Net-(U5A-IN1(+))") (class "Default")
      (node (ref "C10") (pin "2") (pinfunction "2_2") (pintype "passive"))
      (node (ref "R38") (pin "2") (pinfunction "2_2") (pintype "passive"))
      (node (ref "U5") (pin "3") (pinfunction "IN1(+)_3") (pintype "input"))
    )
    (net (code "62") (name "Net-(U5A-IN1(-))") (class "Default")
      (node (ref "R33") (pin "1") (pinfunction "1_1") (pintype "passive"))
      (node (ref "R34") (pin "2") (pinfunction "2_2") (pintype "passive"))
      (node (ref "U5") (pin "2") (pinfunction "IN1(-)_2") (pintype "input"))
    )
    (net (code "63") (name "Net-(U5B-IN2(+))") (class "Default")
      (node (ref "R36") (pin "1") (pinfunction "1_1") (pintype "passive"))
      (node (ref "R39") (pin "2") (pinfunction "2_2") (pintype "passive"))
      (node (ref "R40") (pin "2") (pinfunction "2_2") (pintype "passive"))
      (node (ref "U5") (pin "5") (pinfunction "IN2(+)_5") (pintype "input"))
    )
    (net (code "64") (name "VCC") (class "Default")
      (node (ref "J20") (pin "1") (pinfunction "1_1") (pintype "passive"))
      (node (ref "J20") (pin "2") (pinfunction "2_2") (pintype "passive"))
      (node (ref "J20") (pin "3") (pinfunction "3_3") (pintype "passive"))
      (node (ref "P1") (pin "1") (pinfunction "1_1") (pintype "passive"))
      (node (ref "R11") (pin "2") (pinfunction "2_2") (pintype "passive"))
      (node (ref "R12") (pin "2") (pinfunction "2_2") (pintype "passive"))
      (node (ref "R19") (pin "2") (pinfunction "2_2") (pintype "passive"))
      (node (ref "R20") (pin "2") (pinfunction "2_2") (pintype "passive"))
      (node (ref "R27") (pin "2") (pinfunction "2_2") (pintype "passive"))
      (node (ref "R28") (pin "2") (pinfunction "2_2") (pintype "passive"))
      (node (ref "R3") (pin "2") (pinfunction "2_2") (pintype "passive"))
      (node (ref "R35") (pin "2") (pinfunction "2_2") (pintype "passive"))
      (node (ref "R36") (pin "2") (pinfunction "2_2") (pintype "passive"))
      (node (ref "R4") (pin "2") (pinfunction "2_2") (pintype "passive"))
      (node (ref "S1") (pin "3") (pinfunction "B2_3") (pintype "passive"))
      (node (ref "S1") (pin "4") (pinfunction "B1_4") (pintype "passive"))
      (node (ref "S2") (pin "3") (pinfunction "B2_3") (pintype "passive"))
      (node (ref "S2") (pin "4") (pinfunction "B1_4") (pintype "passive"))
      (node (ref "U1") (pin "8") (pinfunction "VCC_8") (pintype "power_in"))
      (node (ref "U2") (pin "8") (pinfunction "VCC_8") (pintype "power_in"))
      (node (ref "U3") (pin "8") (pinfunction "VCC_8") (pintype "power_in"))
      (node (ref "U4") (pin "8") (pinfunction "VCC_8") (pintype "power_in"))
      (node (ref "U5") (pin "8") (pinfunction "VCC_8") (pintype "power_in"))
    )
    (net (code "65") (name "unconnected-(J2-Pad4)") (class "Default")
      (node (ref "J2") (pin "4") (pinfunction "4_4") (pintype "passive"))
    )
    (net (code "66") (name "unconnected-(J2-Pad5)") (class "Default")
      (node (ref "J2") (pin "5") (pinfunction "5_5") (pintype "passive"))
    )
    (net (code "67") (name "unconnected-(J9-Pad2)") (class "Default")
      (node (ref "J9") (pin "2") (pinfunction "2_2") (pintype "passive"))
    )
    (net (code "68") (name "unconnected-(J9-Pad11)") (class "Default")
      (node (ref "J9") (pin "11") (pinfunction "11_11") (pintype "passive"))
    )
    (net (code "69") (name "unconnected-(J9-Pad12)") (class "Default")
      (node (ref "J9") (pin "12") (pinfunction "12_12") (pintype "passive"))
    )
    (net (code "70") (name "unconnected-(J9-Pad13)") (class "Default")
      (node (ref "J9") (pin "13") (pinfunction "13_13") (pintype "passive"))
    )
    (net (code "71") (name "unconnected-(J9-Pad14)") (class "Default")
      (node (ref "J9") (pin "14") (pinfunction "14_14") (pintype "passive"))
    )
    (net (code "72") (name "unconnected-(J9-Pad15)") (class "Default")
      (node (ref "J9") (pin "15") (pinfunction "15_15") (pintype "passive"))
    )
    (net (code "73") (name "unconnected-(J9-Pad16)") (class "Default")
      (node (ref "J9") (pin "16") (pinfunction "16_16") (pintype "passive"))
    )
    (net (code "74") (name "unconnected-(J9-Pad17)") (class "Default")
      (node (ref "J9") (pin "17") (pinfunction "17_17") (pintype "passive"))
    )
    (net (code "75") (name "unconnected-(J9-Pad18)") (class "Default")
      (node (ref "J9") (pin "18") (pinfunction "18_18") (pintype "passive"))
    )
    (net (code "76") (name "unconnected-(J9-Pad20)") (class "Default")
      (node (ref "J9") (pin "20") (pinfunction "20_20") (pintype "passive"))
    )
    (net (code "77") (name "unconnected-(J9-Pad26)") (class "Default")
      (node (ref "J9") (pin "26") (pinfunction "26_26") (pintype "passive"))
    )
    (net (code "78") (name "unconnected-(J10-Pad1)") (class "Default")
      (node (ref "J10") (pin "1") (pinfunction "1_1") (pintype "passive"))
    )
    (net (code "79") (name "unconnected-(J10-Pad3)") (class "Default")
      (node (ref "J10") (pin "3") (pinfunction "3_3") (pintype "passive"))
    )
    (net (code "80") (name "unconnected-(J10-Pad5)") (class "Default")
      (node (ref "J10") (pin "5") (pinfunction "5_5") (pintype "passive"))
    )
    (net (code "81") (name "unconnected-(J10-Pad6)") (class "Default")
      (node (ref "J10") (pin "6") (pinfunction "6_6") (pintype "passive"))
    )
    (net (code "82") (name "unconnected-(J10-Pad7)") (class "Default")
      (node (ref "J10") (pin "7") (pinfunction "7_7") (pintype "passive"))
    )
    (net (code "83") (name "unconnected-(J10-Pad8)") (class "Default")
      (node (ref "J10") (pin "8") (pinfunction "8_8") (pintype "passive"))
    )
    (net (code "84") (name "unconnected-(J10-Pad19)") (class "Default")
      (node (ref "J10") (pin "19") (pinfunction "19_19") (pintype "passive"))
    )
    (net (code "85") (name "unconnected-(J10-Pad20)") (class "Default")
      (node (ref "J10") (pin "20") (pinfunction "20_20") (pintype "passive"))
    )
    (net (code "86") (name "unconnected-(J10-Pad21)") (class "Default")
      (node (ref "J10") (pin "21") (pinfunction "21_21") (pintype "passive"))
    )
    (net (code "87") (name "unconnected-(J10-Pad22)") (class "Default")
      (node (ref "J10") (pin "22") (pinfunction "22_22") (pintype "passive"))
    )
    (net (code "88") (name "unconnected-(J10-Pad23)") (class "Default")
      (node (ref "J10") (pin "23") (pinfunction "23_23") (pintype "passive"))
    )
    (net (code "89") (name "unconnected-(P2-Pad1)") (class "Default")
      (node (ref "P2") (pin "1") (pinfunction "1_1") (pintype "passive"))
    )
  )
)
